# clock_generator.net
KiCad netlist of a schematic drawn in EAGLE
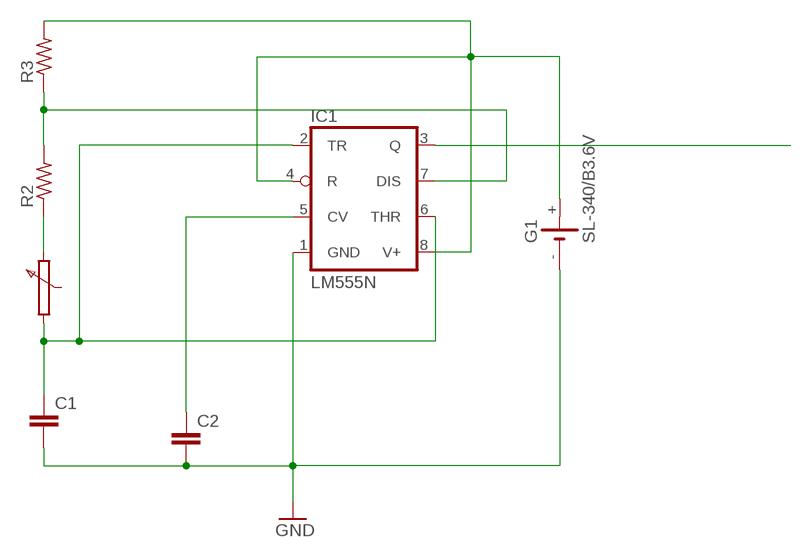
[diagram p0: schematic, sheet 1]

(export (version "E")
  (design (tool "Eeschema 10.0.6"))
  (components
    (comp (ref "C1")
      (value "C2,5-3")
      (footprint "eagle-import:C2.5-3")
      (libsource (lib "eagle-import") (part "C2,5-3"))
    )
    (comp (ref "C2")
      (value "C2,5-3")
      (footprint "eagle-import:C2.5-3")
      (libsource (lib "eagle-import") (part "C2,5-3"))
    )
    (comp (ref "G1")
      (value "SL-340/B3.6V")
      (footprint "eagle-import:SL-340_B3.6V")
      (libsource (lib "eagle-import") (part "SL-340/B3.6V"))
    )
    (comp (ref "IC1")
      (value "LM555N")
      (footprint "eagle-import:DIL08-ROUND")
      (libsource (lib "eagle-import") (part "555NLM"))
    )
    (comp (ref "R2")
      (value "R-US_0204/7")
      (footprint "eagle-import:0204_7")
      (libsource (lib "eagle-import") (part "R-US_0204/7"))
    )
    (comp (ref "R3")
      (value "R-US_0204/7")
      (footprint "eagle-import:0204_7")
      (libsource (lib "eagle-import") (part "R-US_0204/7"))
    )
  )
  (nets
    (net (code "1") (name "GND") (class "Default")
      (node (ref "C1") (pin "2") (pinfunction "2_2") (pintype "passive"))
      (node (ref "C2") (pin "2") (pinfunction "2_2") (pintype "passive"))
      (node (ref "G1") (pin "-") (pinfunction "-_-") (pintype "passive"))
      (node (ref "IC1") (pin "1") (pinfunction "GND_1") (pintype "power_in"))
    )
    (net (code "2") (name "Net-(IC1-CV)") (class "Default")
      (node (ref "C2") (pin "1") (pinfunction "1_1") (pintype "passive"))
      (node (ref "IC1") (pin "5") (pinfunction "CV_5") (pintype "input"))
    )
    (net (code "3") (name "Net-(IC1-DIS)") (class "Default")
      (node (ref "IC1") (pin "7") (pinfunction "DIS_7") (pintype "input"))
      (node (ref "R2") (pin "2") (pinfunction "2_2") (pintype "passive"))
      (node (ref "R3") (pin "1") (pinfunction "1_1") (pintype "passive"))
    )
    (net (code "4") (name "Net-(IC1-R)") (class "Default")
      (node (ref "G1") (pin "+") (pinfunction "+_+") (pintype "passive"))
      (node (ref "IC1") (pin "4") (pinfunction "R_4") (pintype "input"))
      (node (ref "IC1") (pin "8") (pinfunction "V+_8") (pintype "power_in"))
      (node (ref "R3") (pin "2") (pinfunction "2_2") (pintype "passive"))
    )
    (net (code "5") (name "Net-(IC1-THR)") (class "Default")
      (node (ref "C1") (pin "1") (pinfunction "1_1") (pintype "passive"))
      (node (ref "IC1") (pin "2") (pinfunction "TR_2") (pintype "input"))
      (node (ref "IC1") (pin "6") (pinfunction "THR_6") (pintype "input"))
    )
    (net (code "6") (name "unconnected-(IC1-Q-Pad3)") (class "Default")
      (node (ref "IC1") (pin "3") (pinfunction "Q_3") (pintype "output"))
    )
    (net (code "7") (name "unconnected-(R2-Pad1)") (class "Default")
      (node (ref "R2") (pin "1") (pinfunction "1_1") (pintype "passive"))
    )
  )
)
